# design.net
KiCad netlist of a schematic drawn in EasyEDA Pro
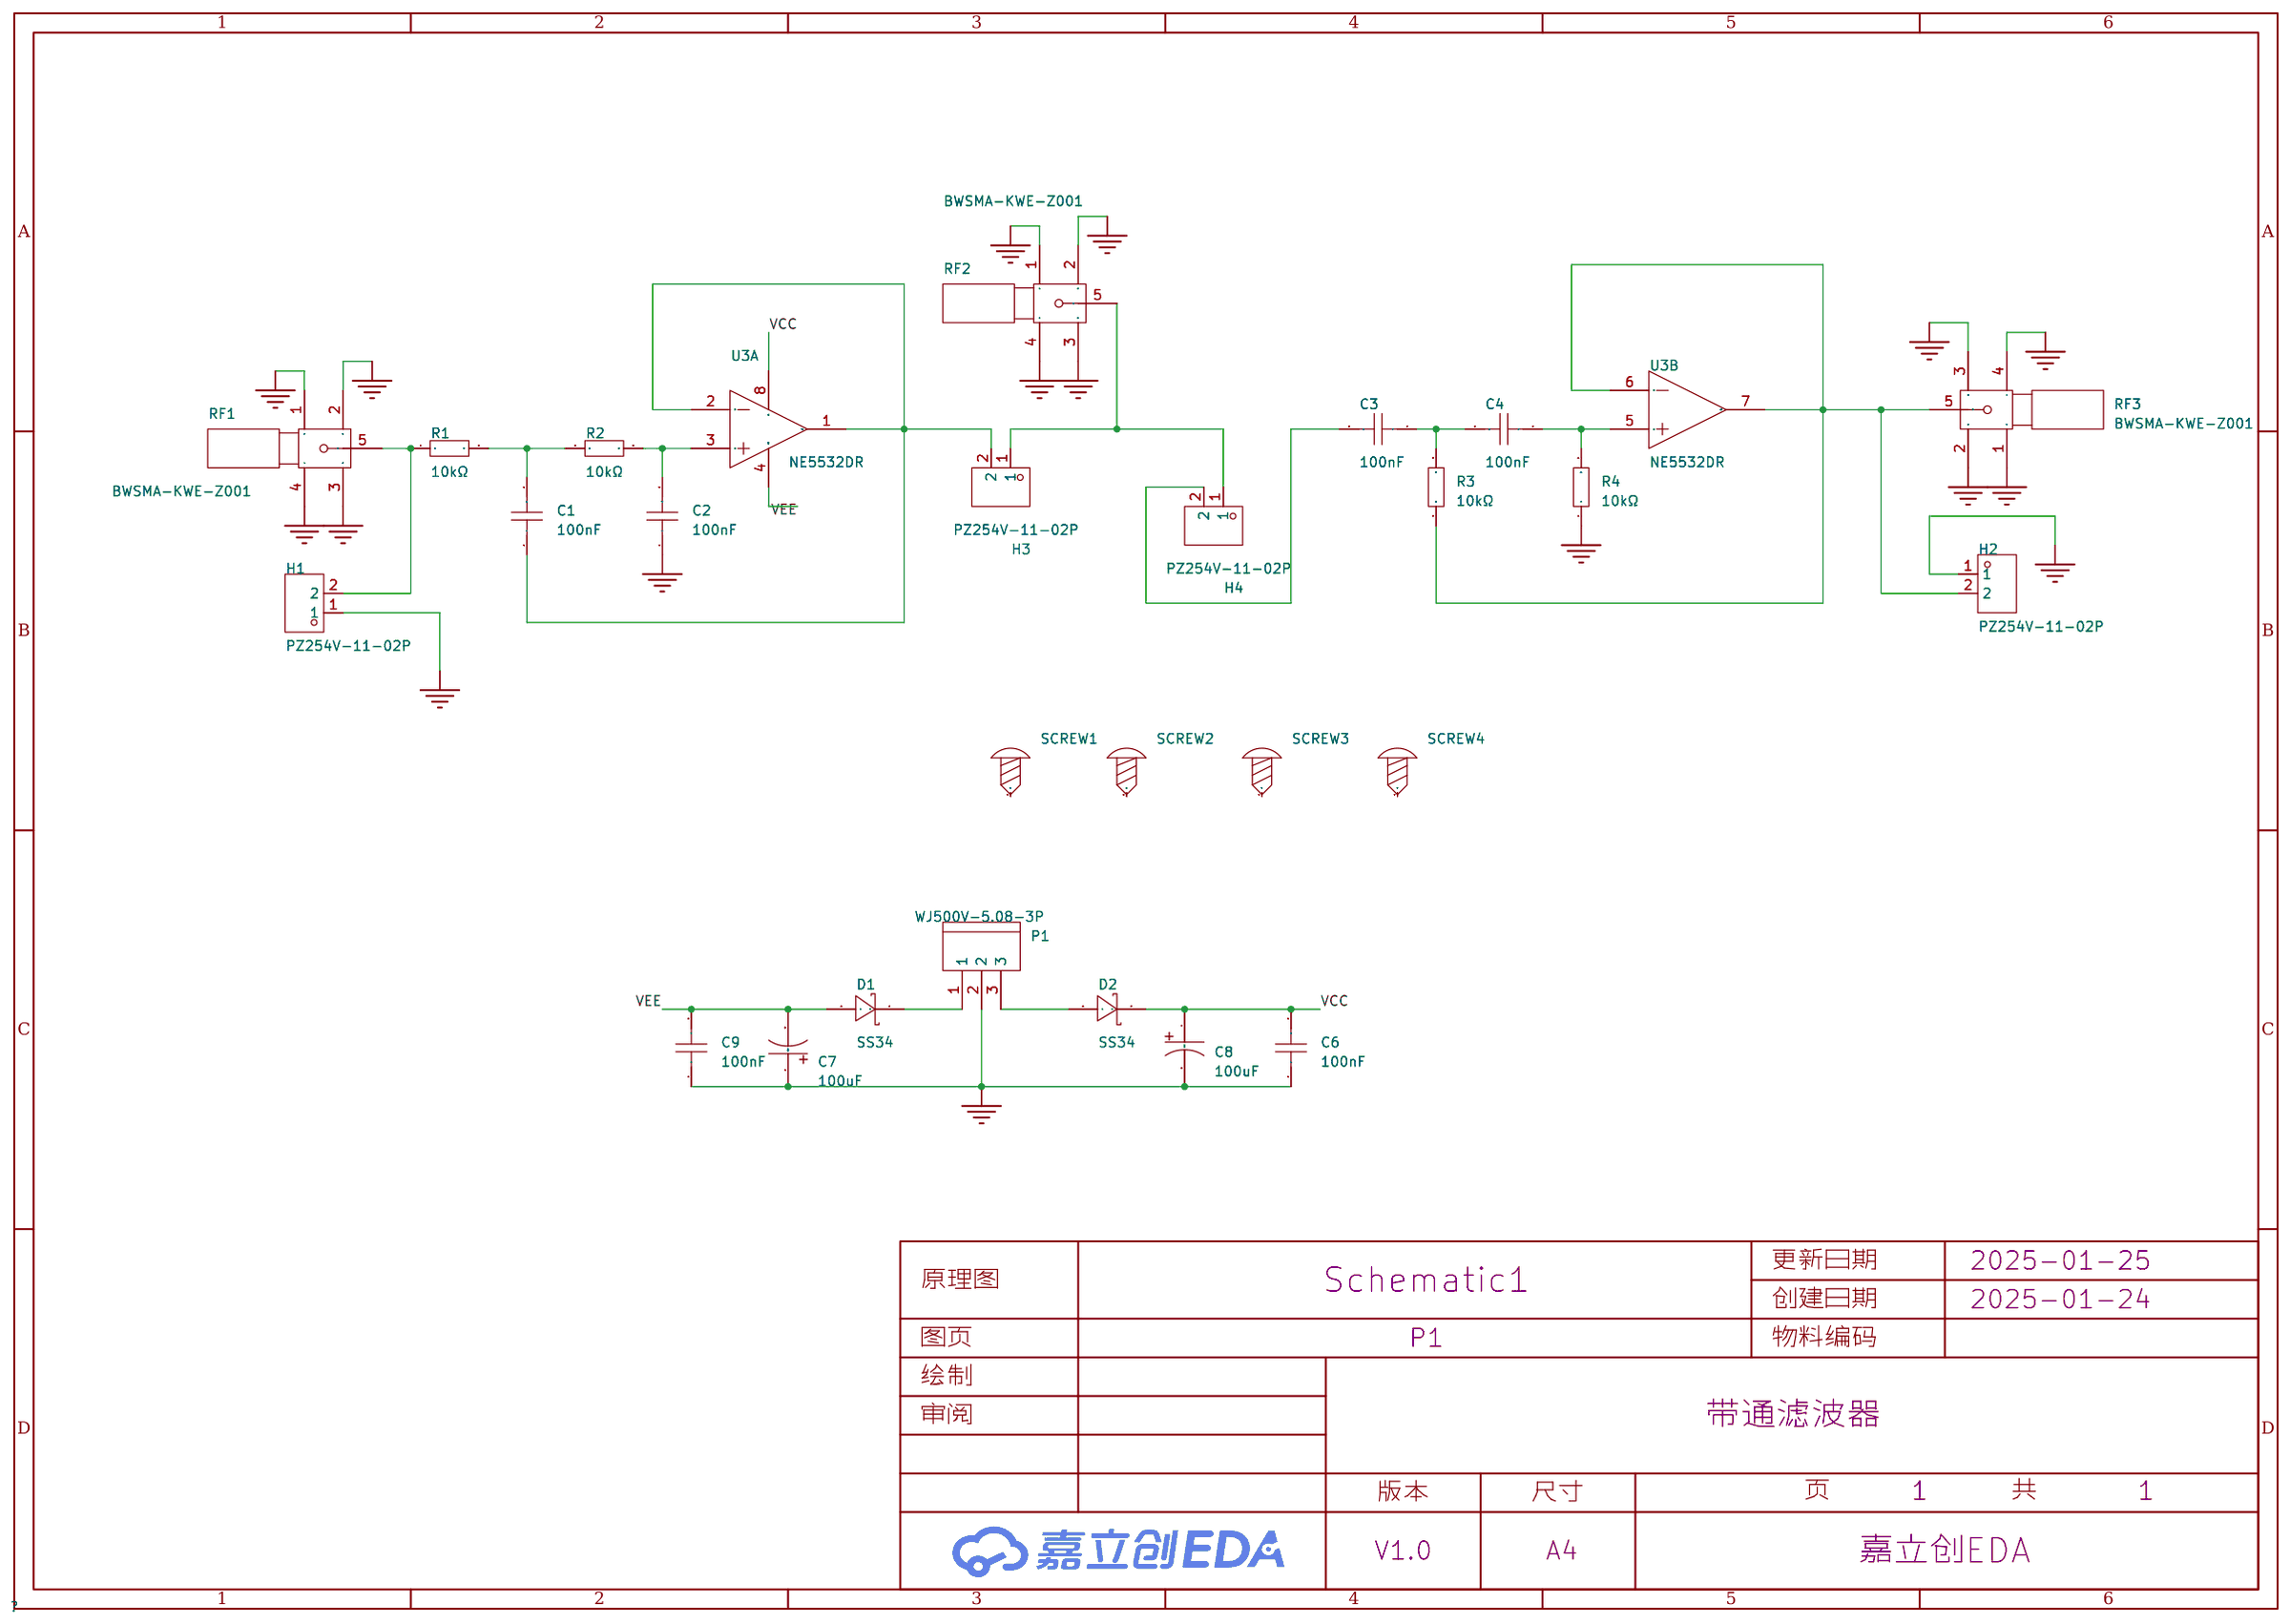
[diagram p0: schematic sheet]

(export (version "E")
  (design (tool "Eeschema 10.0.6"))
  (components
    (comp (ref "C1")
      (value "100nF")
      (footprint "easyedapro:C0603")
      (fields
        (field (name "Manufacturer Part") "CC0805KRX7R9BB104")
        (field (name "Manufacturer") "YAGEO(国巨)")
      )
      (libsource (lib "easyedapro") (part "CapAcitance"))
    )
    (comp (ref "C2")
      (value "100nF")
      (footprint "easyedapro:C0603")
      (fields
        (field (name "Manufacturer Part") "CC0805KRX7R9BB104")
        (field (name "Manufacturer") "YAGEO(国巨)")
      )
      (libsource (lib "easyedapro") (part "CapAcitance"))
    )
    (comp (ref "C3")
      (value "100nF")
      (footprint "easyedapro:C0603")
      (fields
        (field (name "Manufacturer Part") "CC0805KRX7R9BB104")
        (field (name "Manufacturer") "YAGEO(国巨)")
      )
      (libsource (lib "easyedapro") (part "CapAcitance"))
    )
    (comp (ref "C4")
      (value "100nF")
      (footprint "easyedapro:C0603")
      (fields
        (field (name "Manufacturer Part") "CC0805KRX7R9BB104")
        (field (name "Manufacturer") "YAGEO(国巨)")
      )
      (libsource (lib "easyedapro") (part "CapAcitance"))
    )
    (comp (ref "C6")
      (value "100nF")
      (footprint "easyedapro:C0603")
      (libsource (lib "easyedapro") (part "CapAcitance"))
    )
    (comp (ref "C7")
      (value "100uF")
      (footprint "easyedapro:CAP-SMD_BD6.3-L6.6-W6.6-FD")
      (description "容值:100uF;精度:±20%;额定电压:35V;")
      (fields (field (name "Manufacturer Part") "EEHZK1V101XP") (field (name "Manufacturer") "PANASONIC(松下)"))
      (libsource (lib "easyedapro") (part "EEHZK1V101XP"))
    )
    (comp (ref "C8")
      (value "100uF")
      (footprint "easyedapro:CAP-SMD_BD6.3-L6.6-W6.6-FD")
      (description "容值:100uF;精度:±20%;额定电压:35V;")
      (fields (field (name "Manufacturer Part") "EEHZK1V101XP") (field (name "Manufacturer") "PANASONIC(松下)"))
      (libsource (lib "easyedapro") (part "EEHZK1V101XP"))
    )
    (comp (ref "C9")
      (value "100nF")
      (footprint "easyedapro:C0603")
      (libsource (lib "easyedapro") (part "CapAcitance"))
    )
    (comp (ref "D1")
      (value "SS34")
      (footprint "easyedapro:SMA_L4.3-W2.6-LS5.2-RD")
      (description "二极管配置:独立式;正向压降(Vf):550mV@3A;直流反向耐压(Vr):40V;整流电流:3A;")
      (fields (field (name "Manufacturer") "MDD(辰达半导体)"))
      (libsource (lib "easyedapro") (part "SS34_C8678"))
    )
    (comp (ref "D2")
      (value "SS34")
      (footprint "easyedapro:SMA_L4.3-W2.6-LS5.2-RD")
      (description "二极管配置:独立式;正向压降(Vf):550mV@3A;直流反向耐压(Vr):40V;整流电流:3A;")
      (fields (field (name "Manufacturer") "MDD(辰达半导体)"))
      (libsource (lib "easyedapro") (part "SS34_C8678"))
    )
    (comp (ref "H1")
      (value "PZ254V-11-02P")
      (footprint "easyedapro:HDR-TH_2P-P2.54-V-M")
      (fields (field (name "Manufacturer") "XFCN(兴飞)"))
      (libsource (lib "easyedapro") (part "PZ254V-11-02P"))
    )
    (comp (ref "H2")
      (value "PZ254V-11-02P")
      (footprint "easyedapro:HDR-TH_2P-P2.54-V-M")
      (fields (field (name "Manufacturer") "XFCN(兴飞)"))
      (libsource (lib "easyedapro") (part "PZ254V-11-02P"))
    )
    (comp (ref "H3")
      (value "PZ254V-11-02P")
      (footprint "easyedapro:HDR-TH_2P-P2.54-V-M")
      (fields (field (name "Manufacturer") "XFCN(兴飞)"))
      (libsource (lib "easyedapro") (part "PZ254V-11-02P"))
    )
    (comp (ref "H4")
      (value "PZ254V-11-02P")
      (footprint "easyedapro:HDR-TH_2P-P2.54-V-M")
      (fields (field (name "Manufacturer") "XFCN(兴飞)"))
      (libsource (lib "easyedapro") (part "PZ254V-11-02P"))
    )
    (comp (ref "P1")
      (value "WJ500V-5.08-3P")
      (footprint "easyedapro:CONN-TH_3P-P5.00_WJ500V-5.08-3P")
      (fields (field (name "Manufacturer") "KANGNEX(康奈克斯电气)"))
      (libsource (lib "easyedapro") (part "WJ500V-5.08-3P-14-00A"))
    )
    (comp (ref "R1")
      (value "10kΩ")
      (footprint "easyedapro:R0603")
      (fields
        (field (name "Manufacturer Part") "0805W8F1002T5E")
        (field (name "Manufacturer") "UNI-ROYAL(厚声)")
      )
      (libsource (lib "easyedapro") (part "电阻"))
    )
    (comp (ref "R2")
      (value "10kΩ")
      (footprint "easyedapro:R0603")
      (fields
        (field (name "Manufacturer Part") "0805W8F1002T5E")
        (field (name "Manufacturer") "UNI-ROYAL(厚声)")
      )
      (libsource (lib "easyedapro") (part "电阻"))
    )
    (comp (ref "R3")
      (value "10kΩ")
      (footprint "easyedapro:R0603")
      (fields
        (field (name "Manufacturer Part") "0805W8F1002T5E")
        (field (name "Manufacturer") "UNI-ROYAL(厚声)")
      )
      (libsource (lib "easyedapro") (part "电阻"))
    )
    (comp (ref "R4")
      (value "10kΩ")
      (footprint "easyedapro:R0603")
      (fields
        (field (name "Manufacturer Part") "0805W8F1002T5E")
        (field (name "Manufacturer") "UNI-ROYAL(厚声)")
      )
      (libsource (lib "easyedapro") (part "电阻"))
    )
    (comp (ref "RF1")
      (value "BWSMA-KWE-Z001")
      (footprint "easyedapro:SMA-TH_BWSMA-KWE-Z001")
      (fields (field (name "Manufacturer") "BAT WIRELESS(蝙蝠无线)"))
      (libsource (lib "easyedapro") (part "BWSMA-KWE-Z001"))
    )
    (comp (ref "RF2")
      (value "BWSMA-KWE-Z001")
      (footprint "easyedapro:SMA-TH_BWSMA-KWE-Z001")
      (fields (field (name "Manufacturer") "BAT WIRELESS(蝙蝠无线)"))
      (libsource (lib "easyedapro") (part "BWSMA-KWE-Z001"))
    )
    (comp (ref "RF3")
      (value "BWSMA-KWE-Z001")
      (footprint "easyedapro:SMA-TH_BWSMA-KWE-Z001")
      (fields (field (name "Manufacturer") "BAT WIRELESS(蝙蝠无线)"))
      (libsource (lib "easyedapro") (part "BWSMA-KWE-Z001"))
    )
    (comp (ref "SCREW1")
      (value "~")
      (footprint "easyedapro:M3螺丝")
      (libsource (lib "easyedapro") (part "螺丝孔"))
    )
    (comp (ref "SCREW2")
      (value "~")
      (footprint "easyedapro:M3螺丝")
      (libsource (lib "easyedapro") (part "螺丝孔"))
    )
    (comp (ref "SCREW3")
      (value "~")
      (footprint "easyedapro:M3螺丝")
      (libsource (lib "easyedapro") (part "螺丝孔"))
    )
    (comp (ref "SCREW4")
      (value "~")
      (footprint "easyedapro:M3螺丝")
      (libsource (lib "easyedapro") (part "螺丝孔"))
    )
    (comp (ref "U3")
      (value "NE5532DR")
      (footprint "easyedapro:SOIC-8_L4.9-W3.9-P1.27-LS6.0-BL")
      (description "放大器数:双路;增益带宽积(GBP):10MHz;输入偏置电流(Ib):200nA;压摆率(SR):9V/us;带宽(-3db):-;")
      (fields (field (name "Manufacturer") "TI(德州仪器)"))
      (libsource (lib "easyedapro") (part "NE5532DR"))
    )
  )
  (nets
    (net (code "1") (name "/VCC") (class "Default")
      (node (ref "C6") (pin "2") (pinfunction "2_2") (pintype "input"))
      (node (ref "C8") (pin "1") (pinfunction "1_1") (pintype "unspecified"))
      (node (ref "D2") (pin "1") (pinfunction "K_1") (pintype "unspecified"))
      (node (ref "U3") (pin "8") (pinfunction "VCC+_8") (pintype "unspecified"))
    )
    (net (code "2") (name "/VEE") (class "Default")
      (node (ref "C7") (pin "2") (pinfunction "2_2") (pintype "unspecified"))
      (node (ref "C9") (pin "2") (pinfunction "2_2") (pintype "input"))
      (node (ref "D1") (pin "2") (pinfunction "A_2") (pintype "unspecified"))
      (node (ref "U3") (pin "4") (pinfunction "VCC-/GND_4") (pintype "unspecified"))
    )
    (net (code "3") (name "GND") (class "Default")
      (node (ref "C2") (pin "1") (pinfunction "1_1") (pintype "input"))
      (node (ref "C6") (pin "1") (pinfunction "1_1") (pintype "input"))
      (node (ref "C7") (pin "1") (pinfunction "1_1") (pintype "unspecified"))
      (node (ref "C8") (pin "2") (pinfunction "2_2") (pintype "unspecified"))
      (node (ref "C9") (pin "1") (pinfunction "1_1") (pintype "input"))
      (node (ref "H1") (pin "1") (pinfunction "1_1") (pintype "unspecified"))
      (node (ref "H2") (pin "1") (pinfunction "1_1") (pintype "unspecified"))
      (node (ref "P1") (pin "2") (pinfunction "2_2") (pintype "unspecified"))
      (node (ref "R4") (pin "1") (pinfunction "1_1") (pintype "input"))
      (node (ref "RF1") (pin "1") (pinfunction "1_1") (pintype "unspecified"))
      (node (ref "RF1") (pin "2") (pinfunction "2_2") (pintype "unspecified"))
      (node (ref "RF1") (pin "3") (pinfunction "3_3") (pintype "unspecified"))
      (node (ref "RF1") (pin "4") (pinfunction "4_4") (pintype "unspecified"))
      (node (ref "RF2") (pin "1") (pinfunction "1_1") (pintype "unspecified"))
      (node (ref "RF2") (pin "2") (pinfunction "2_2") (pintype "unspecified"))
      (node (ref "RF2") (pin "3") (pinfunction "3_3") (pintype "unspecified"))
      (node (ref "RF2") (pin "4") (pinfunction "4_4") (pintype "unspecified"))
      (node (ref "RF3") (pin "1") (pinfunction "1_1") (pintype "unspecified"))
      (node (ref "RF3") (pin "2") (pinfunction "2_2") (pintype "unspecified"))
      (node (ref "RF3") (pin "3") (pinfunction "3_3") (pintype "unspecified"))
      (node (ref "RF3") (pin "4") (pinfunction "4_4") (pintype "unspecified"))
    )
    (net (code "4") (name "Net-(C1-Pad2)") (class "Default")
      (node (ref "C1") (pin "2") (pinfunction "2_2") (pintype "input"))
      (node (ref "R1") (pin "2") (pinfunction "2_2") (pintype "input"))
      (node (ref "R2") (pin "1") (pinfunction "1_1") (pintype "input"))
    )
    (net (code "5") (name "Net-(C3-Pad1)") (class "Default")
      (node (ref "C3") (pin "1") (pinfunction "1_1") (pintype "input"))
      (node (ref "C4") (pin "2") (pinfunction "2_2") (pintype "input"))
      (node (ref "R3") (pin "2") (pinfunction "2_2") (pintype "input"))
    )
    (net (code "6") (name "Net-(C3-Pad2)") (class "Default")
      (node (ref "C3") (pin "2") (pinfunction "2_2") (pintype "input"))
      (node (ref "H4") (pin "2") (pinfunction "2_2") (pintype "unspecified"))
    )
    (net (code "7") (name "Net-(D1-K)") (class "Default")
      (node (ref "D1") (pin "1") (pinfunction "K_1") (pintype "unspecified"))
      (node (ref "P1") (pin "1") (pinfunction "1_1") (pintype "unspecified"))
    )
    (net (code "8") (name "Net-(D2-A)") (class "Default")
      (node (ref "D2") (pin "2") (pinfunction "A_2") (pintype "unspecified"))
      (node (ref "P1") (pin "3") (pinfunction "3_3") (pintype "unspecified"))
    )
    (net (code "9") (name "Net-(H1-Pad2)") (class "Default")
      (node (ref "H1") (pin "2") (pinfunction "2_2") (pintype "unspecified"))
      (node (ref "R1") (pin "1") (pinfunction "1_1") (pintype "input"))
      (node (ref "RF1") (pin "5") (pinfunction "5_5") (pintype "unspecified"))
    )
    (net (code "10") (name "Net-(H3-Pad1)") (class "Default")
      (node (ref "H3") (pin "1") (pinfunction "1_1") (pintype "unspecified"))
      (node (ref "H4") (pin "1") (pinfunction "1_1") (pintype "unspecified"))
      (node (ref "RF2") (pin "5") (pinfunction "5_5") (pintype "unspecified"))
    )
    (net (code "11") (name "Net-(U3A-IN1+)") (class "Default")
      (node (ref "C2") (pin "2") (pinfunction "2_2") (pintype "input"))
      (node (ref "R2") (pin "2") (pinfunction "2_2") (pintype "input"))
      (node (ref "U3") (pin "3") (pinfunction "IN1+_3") (pintype "unspecified"))
    )
    (net (code "12") (name "Net-(U3A-IN1-)") (class "Default")
      (node (ref "C1") (pin "1") (pinfunction "1_1") (pintype "input"))
      (node (ref "H3") (pin "2") (pinfunction "2_2") (pintype "unspecified"))
      (node (ref "U3") (pin "1") (pinfunction "OUT1_1") (pintype "output"))
      (node (ref "U3") (pin "2") (pinfunction "IN1-_2") (pintype "unspecified"))
    )
    (net (code "13") (name "Net-(U3B-IN2+)") (class "Default")
      (node (ref "C4") (pin "1") (pinfunction "1_1") (pintype "input"))
      (node (ref "R4") (pin "2") (pinfunction "2_2") (pintype "input"))
      (node (ref "U3") (pin "5") (pinfunction "IN2+_5") (pintype "unspecified"))
    )
    (net (code "14") (name "Net-(U3B-IN2-)") (class "Default")
      (node (ref "H2") (pin "2") (pinfunction "2_2") (pintype "unspecified"))
      (node (ref "R3") (pin "1") (pinfunction "1_1") (pintype "input"))
      (node (ref "RF3") (pin "5") (pinfunction "5_5") (pintype "unspecified"))
      (node (ref "U3") (pin "6") (pinfunction "IN2-_6") (pintype "unspecified"))
      (node (ref "U3") (pin "7") (pinfunction "OUT2_7") (pintype "output"))
    )
    (net (code "15") (name "unconnected-(SCREW1-Pad1)") (class "Default")
      (node (ref "SCREW1") (pin "1") (pinfunction "1_1") (pintype "input"))
    )
    (net (code "16") (name "unconnected-(SCREW2-Pad1)") (class "Default")
      (node (ref "SCREW2") (pin "1") (pinfunction "1_1") (pintype "input"))
    )
    (net (code "17") (name "unconnected-(SCREW3-Pad1)") (class "Default")
      (node (ref "SCREW3") (pin "1") (pinfunction "1_1") (pintype "input"))
    )
    (net (code "18") (name "unconnected-(SCREW4-Pad1)") (class "Default")
      (node (ref "SCREW4") (pin "1") (pinfunction "1_1") (pintype "input"))
    )
  )
)
